# 555timer_blinker.net
KiCad netlist of a schematic drawn in Altium Designer
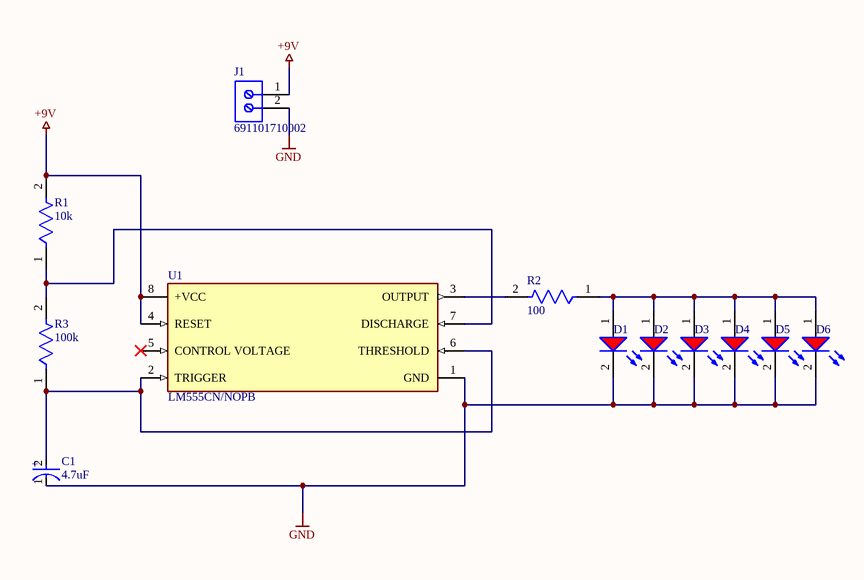
[diagram p0: 555timer_blinker.SchDoc]

(export (version "E")
  (design (tool "Eeschema 10.0.6"))
  (components
    (comp (ref "C1")
      (value "4.7uF")
      (footprint "FP-RAD-TH-D_5_0_5-L_11_1-MFG")
      (description "Aluminum Electrolytic Capacitors (Radial Lead Type) AEC-Q200 Qualified 4.7uF ±20% 50V")
      (fields (field (name "TOLERANCE") "20%"))
      (libsource (lib "Altium Content Vault") (part "a00bbbee19879c290e62620ae7e47b1"))
    )
    (comp (ref "D1")
      (value "151051RS11000")
      (footprint "WL-TMRC_D5.9H8.7")
      (libsource (lib "Altium Content Vault") (part "LED_Red_1A-2K"))
    )
    (comp (ref "D2")
      (value "151051RS11000")
      (footprint "WL-TMRC_D5.9H8.7")
      (libsource (lib "Altium Content Vault") (part "LED_Red_1A-2K"))
    )
    (comp (ref "D3")
      (value "151051RS11000")
      (footprint "WL-TMRC_D5.9H8.7")
      (libsource (lib "Altium Content Vault") (part "LED_Red_1A-2K"))
    )
    (comp (ref "D4")
      (value "151051RS11000")
      (footprint "WL-TMRC_D5.9H8.7")
      (libsource (lib "Altium Content Vault") (part "LED_Red_1A-2K"))
    )
    (comp (ref "D5")
      (value "151051RS11000")
      (footprint "WL-TMRC_D5.9H8.7")
      (libsource (lib "Altium Content Vault") (part "LED_Red_1A-2K"))
    )
    (comp (ref "D6")
      (value "151051RS11000")
      (footprint "WL-TMRC_D5.9H8.7")
      (libsource (lib "Altium Content Vault") (part "LED_Red_1A-2K"))
    )
    (comp (ref "J1")
      (value "691101710002")
      (footprint "691101710002")
      (fields (field (name "VOLTAGE") "250V"))
      (libsource (lib "Altium Content Vault") (part "TBL - 1R - 02P - Screw"))
    )
    (comp (ref "R1")
      (value "10k")
      (footprint "FP-MBB0207-MFG")
      (description "RES 10K OHM 0.6W 1% AXIAL")
      (fields (field (name "TOLERANCE") "1%"))
      (libsource (lib "Altium Content Vault") (part "1029c3af85768c4190bb7ad29bc67b5"))
    )
    (comp (ref "R2")
      (value "100")
      (footprint "FP-MBB0207-MFG")
      (description "RES 10K OHM 0.6W 1% AXIAL")
      (fields (field (name "TOLERANCE") "1%"))
      (libsource (lib "Altium Content Vault") (part "1029c3af85768c4190bb7ad29bc67b5"))
    )
    (comp (ref "R3")
      (value "100k")
      (footprint "FP-MBB0207-MFG")
      (description "RES 10K OHM 0.6W 1% AXIAL")
      (fields (field (name "TOLERANCE") "1%"))
      (libsource (lib "Altium Content Vault") (part "1029c3af85768c4190bb7ad29bc67b5"))
    )
    (comp (ref "U1")
      (value "LM555CN/NOPB")
      (footprint "FP-P0008A-MFG")
      (description "IC OSC SINGLE TIMER 100KHZ 8-DIP")
      (fields
        (field (name "MANUFACTURER") "Texas Instruments")
        (field (name "OCTOPART") "https://octopart.com/lm555cn%2Fnopb-texas+instruments-24814897")
      )
      (libsource (lib "Altium Content Vault") (part "8056d98efc272addb90effbbf338635"))
    )
  )
  (nets
    (net (code "1") (name "+9V") (class "Default")
      (node (ref "J1") (pin "1") (pinfunction "1_1") (pintype "passive"))
      (node (ref "R1") (pin "2") (pinfunction "2_2") (pintype "passive"))
      (node (ref "U1") (pin "4") (pinfunction "RESET_4") (pintype "input"))
      (node (ref "U1") (pin "8") (pinfunction "+VCC_8") (pintype "power_in"))
    )
    (net (code "2") (name "GND") (class "Default")
      (node (ref "C1") (pin "1") (pinfunction "C_1") (pintype "passive"))
      (node (ref "D1") (pin "2") (pinfunction "K_2") (pintype "passive"))
      (node (ref "D2") (pin "2") (pinfunction "K_2") (pintype "passive"))
      (node (ref "D3") (pin "2") (pinfunction "K_2") (pintype "passive"))
      (node (ref "D4") (pin "2") (pinfunction "K_2") (pintype "passive"))
      (node (ref "D5") (pin "2") (pinfunction "K_2") (pintype "passive"))
      (node (ref "D6") (pin "2") (pinfunction "K_2") (pintype "passive"))
      (node (ref "J1") (pin "2") (pinfunction "2_2") (pintype "passive"))
      (node (ref "U1") (pin "1") (pinfunction "GND_1") (pintype "power_in"))
    )
    (net (code "3") (name "Net-(C1-A)") (class "Default")
      (node (ref "C1") (pin "2") (pinfunction "A_2") (pintype "passive"))
      (node (ref "R3") (pin "1") (pinfunction "1_1") (pintype "passive"))
      (node (ref "U1") (pin "2") (pinfunction "TRIGGER_2") (pintype "input"))
      (node (ref "U1") (pin "6") (pinfunction "THRESHOLD_6") (pintype "input"))
    )
    (net (code "4") (name "Net-(D1-A)") (class "Default")
      (node (ref "D1") (pin "1") (pinfunction "A_1") (pintype "passive"))
      (node (ref "D2") (pin "1") (pinfunction "A_1") (pintype "passive"))
      (node (ref "D3") (pin "1") (pinfunction "A_1") (pintype "passive"))
      (node (ref "D4") (pin "1") (pinfunction "A_1") (pintype "passive"))
      (node (ref "D5") (pin "1") (pinfunction "A_1") (pintype "passive"))
      (node (ref "D6") (pin "1") (pinfunction "A_1") (pintype "passive"))
      (node (ref "R2") (pin "1") (pinfunction "1_1") (pintype "passive"))
    )
    (net (code "5") (name "Net-(U1-DISCHARGE)") (class "Default")
      (node (ref "R1") (pin "1") (pinfunction "1_1") (pintype "passive"))
      (node (ref "R3") (pin "2") (pinfunction "2_2") (pintype "passive"))
      (node (ref "U1") (pin "7") (pinfunction "DISCHARGE_7") (pintype "input"))
    )
    (net (code "6") (name "Net-(U1-OUTPUT)") (class "Default")
      (node (ref "R2") (pin "2") (pinfunction "2_2") (pintype "passive"))
      (node (ref "U1") (pin "3") (pinfunction "OUTPUT_3") (pintype "output"))
    )
    (net (code "7") (name "unconnected-(U1-CONTROL_VOLTAGE-Pad5)") (class "Default")
      (node (ref "U1") (pin "5") (pinfunction "CONTROL_VOLTAGE_5") (pintype "input+no_connect"))
    )
  )
)
